# Serial_I2C_Bridge_Prop.net
KiCad netlist of a schematic drawn in EAGLE
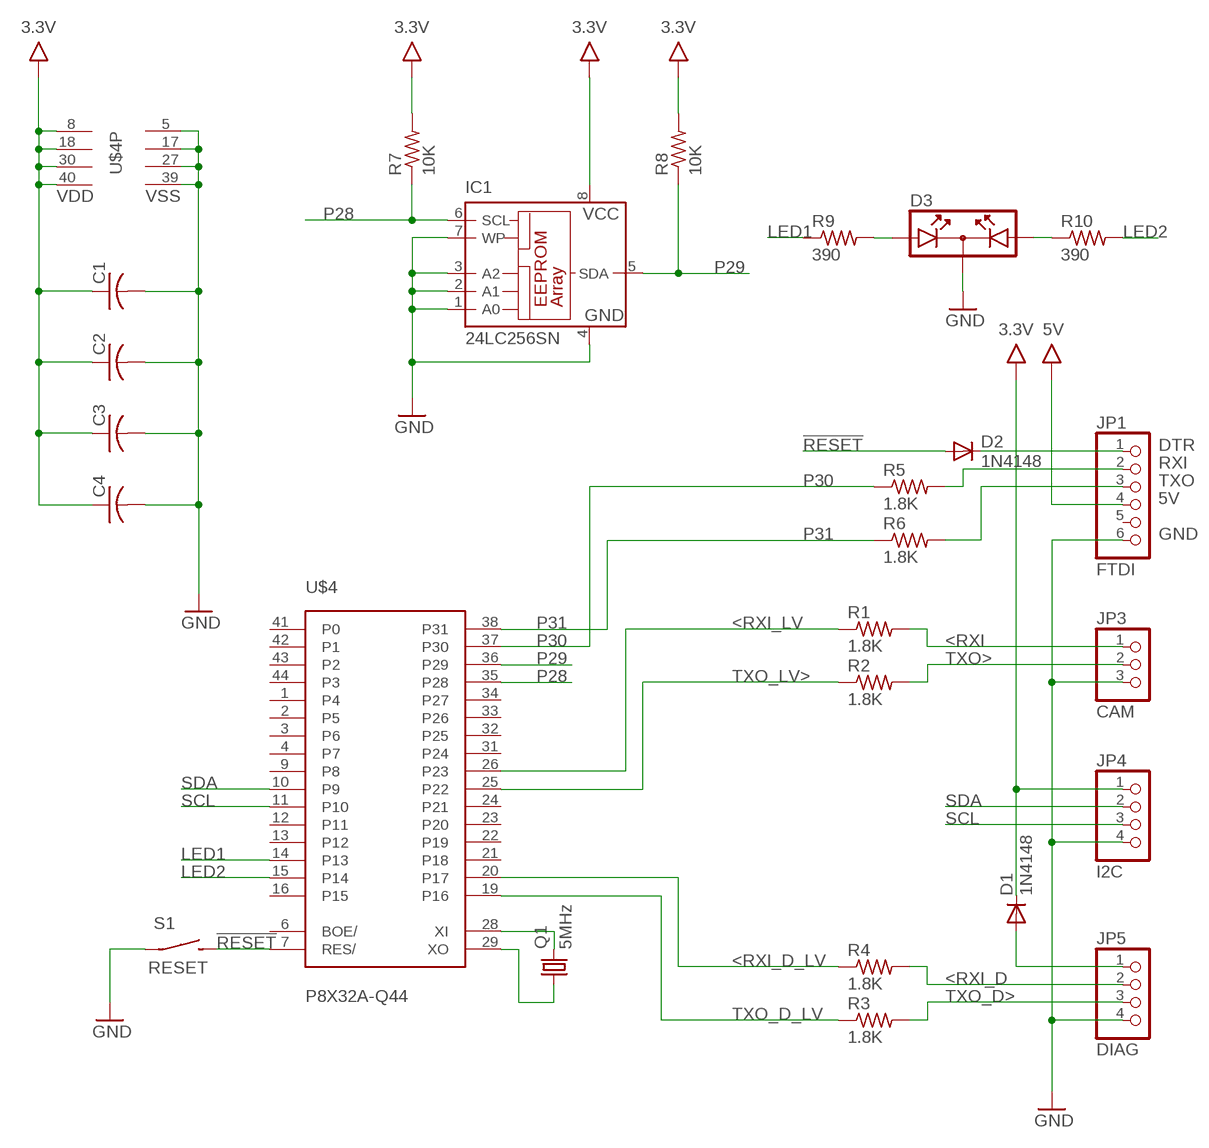
[diagram p0: schematic, sheet 1]

(export (version "E")
  (design (tool "Eeschema 10.0.6"))
  (components
    (comp (ref "C1")
      (value "C-USC0603")
      (footprint "eagle-import:C0603")
      (libsource (lib "eagle-import") (part "C-USC0603"))
    )
    (comp (ref "C2")
      (value "C-USC0603")
      (footprint "eagle-import:C0603")
      (libsource (lib "eagle-import") (part "C-USC0603"))
    )
    (comp (ref "C3")
      (value "C-USC0603")
      (footprint "eagle-import:C0603")
      (libsource (lib "eagle-import") (part "C-USC0603"))
    )
    (comp (ref "C4")
      (value "C-USC0603")
      (footprint "eagle-import:C0603")
      (libsource (lib "eagle-import") (part "C-USC0603"))
    )
    (comp (ref "D1")
      (value "1N4148")
      (footprint "eagle-import:DO35-7")
      (libsource (lib "eagle-import") (part "1N4148DO35-7"))
    )
    (comp (ref "D2")
      (value "1N4148")
      (footprint "eagle-import:DO35-7")
      (libsource (lib "eagle-import") (part "1N4148DO35-7"))
    )
    (comp (ref "D3")
      (value "DUOLED")
      (footprint "eagle-import:DUOLED")
      (libsource (lib "eagle-import") (part "DUOLED"))
    )
    (comp (ref "IC1")
      (value "24LC256SN")
      (footprint "eagle-import:SO-08")
      (fields (field (name "MF") "MICROCHIP") (field (name "MPN") "24LC256-I/SN"))
      (libsource (lib "eagle-import") (part "24SNLC256"))
    )
    (comp (ref "JP1")
      (value "FTDI")
      (footprint "eagle-import:1X06")
      (libsource (lib "eagle-import") (part "PINHD-1X06_2.54"))
    )
    (comp (ref "JP3")
      (value "CAM")
      (footprint "eagle-import:1X03")
      (libsource (lib "eagle-import") (part "PINHD-1X03_2.54"))
    )
    (comp (ref "JP4")
      (value "I2C")
      (footprint "eagle-import:1X04")
      (libsource (lib "eagle-import") (part "PINHD-1X04_2.54"))
    )
    (comp (ref "JP5")
      (value "DIAG")
      (footprint "eagle-import:1X04")
      (libsource (lib "eagle-import") (part "PINHD-1X04_2.54"))
    )
    (comp (ref "Q1")
      (value "5MHz")
      (footprint "eagle-import:HC49_S")
      (libsource (lib "eagle-import") (part "CRYSTALHC49S"))
    )
    (comp (ref "R1")
      (value "1.8K")
      (footprint "eagle-import:0204_5")
      (libsource (lib "eagle-import") (part "R-US_0204/5"))
    )
    (comp (ref "R2")
      (value "1.8K")
      (footprint "eagle-import:0204_5")
      (libsource (lib "eagle-import") (part "R-US_0204/5"))
    )
    (comp (ref "R3")
      (value "1.8K")
      (footprint "eagle-import:0204_5")
      (libsource (lib "eagle-import") (part "R-US_0204/5"))
    )
    (comp (ref "R4")
      (value "1.8K")
      (footprint "eagle-import:0204_5")
      (libsource (lib "eagle-import") (part "R-US_0204/5"))
    )
    (comp (ref "R5")
      (value "1.8K")
      (footprint "eagle-import:0204_5")
      (libsource (lib "eagle-import") (part "R-US_0204/5"))
    )
    (comp (ref "R6")
      (value "1.8K")
      (footprint "eagle-import:0204_5")
      (libsource (lib "eagle-import") (part "R-US_0204/5"))
    )
    (comp (ref "R7")
      (value "10K")
      (footprint "eagle-import:0204_5")
      (libsource (lib "eagle-import") (part "R-US_0204/5"))
    )
    (comp (ref "R8")
      (value "10K")
      (footprint "eagle-import:0204_5")
      (libsource (lib "eagle-import") (part "R-US_0204/5"))
    )
    (comp (ref "R9")
      (value "390")
      (footprint "eagle-import:0204_5")
      (libsource (lib "eagle-import") (part "R-US_0204/5"))
    )
    (comp (ref "R10")
      (value "390")
      (footprint "eagle-import:0204_5")
      (libsource (lib "eagle-import") (part "R-US_0204/5"))
    )
    (comp (ref "S1")
      (value "RESET")
      (footprint "eagle-import:6MMTACTILE")
      (libsource (lib "eagle-import") (part "SPSTTACTILE2"))
    )
    (comp (ref "U$4")
      (value "P8X32A-Q44")
      (footprint "eagle-import:P8X32A-Q44")
      (libsource (lib "eagle-import") (part "P8X32A-Q44"))
    )
  )
  (nets
    (net (code "1") (name "/<RXI") (class "Default")
      (node (ref "JP3") (pin "1") (pinfunction "1_1") (pintype "passive"))
      (node (ref "R1") (pin "2") (pinfunction "2_2") (pintype "passive"))
    )
    (net (code "2") (name "/<RXI_D") (class "Default")
      (node (ref "JP5") (pin "2") (pinfunction "2_2") (pintype "passive"))
      (node (ref "R4") (pin "2") (pinfunction "2_2") (pintype "passive"))
    )
    (net (code "3") (name "/<RXI_D_LV") (class "Default")
      (node (ref "R4") (pin "1") (pinfunction "1_1") (pintype "passive"))
      (node (ref "U$4") (pin "20") (pinfunction "P17_20") (pintype "bidirectional"))
    )
    (net (code "4") (name "/<RXI_LV") (class "Default")
      (node (ref "R1") (pin "1") (pinfunction "1_1") (pintype "passive"))
      (node (ref "U$4") (pin "26") (pinfunction "P23_26") (pintype "bidirectional"))
    )
    (net (code "5") (name "/LED1") (class "Default")
      (node (ref "R9") (pin "1") (pinfunction "1_1") (pintype "passive"))
      (node (ref "U$4") (pin "14") (pinfunction "P13_14") (pintype "bidirectional"))
    )
    (net (code "6") (name "/LED2") (class "Default")
      (node (ref "R10") (pin "2") (pinfunction "2_2") (pintype "passive"))
      (node (ref "U$4") (pin "15") (pinfunction "P14_15") (pintype "bidirectional"))
    )
    (net (code "7") (name "/P28") (class "Default")
      (node (ref "IC1") (pin "6") (pinfunction "SCL_6") (pintype "input"))
      (node (ref "R7") (pin "1") (pinfunction "1_1") (pintype "passive"))
      (node (ref "U$4") (pin "35") (pinfunction "P28_35") (pintype "bidirectional"))
    )
    (net (code "8") (name "/P29") (class "Default")
      (node (ref "IC1") (pin "5") (pinfunction "SDA_5") (pintype "bidirectional"))
      (node (ref "R8") (pin "1") (pinfunction "1_1") (pintype "passive"))
      (node (ref "U$4") (pin "36") (pinfunction "P29_36") (pintype "bidirectional"))
    )
    (net (code "9") (name "/P30") (class "Default")
      (node (ref "R5") (pin "1") (pinfunction "1_1") (pintype "passive"))
      (node (ref "U$4") (pin "37") (pinfunction "P30_37") (pintype "bidirectional"))
    )
    (net (code "10") (name "/P31") (class "Default")
      (node (ref "R6") (pin "1") (pinfunction "1_1") (pintype "passive"))
      (node (ref "U$4") (pin "38") (pinfunction "P31_38") (pintype "bidirectional"))
    )
    (net (code "11") (name "/SCL") (class "Default")
      (node (ref "JP4") (pin "3") (pinfunction "3_3") (pintype "passive"))
      (node (ref "U$4") (pin "11") (pinfunction "P10_11") (pintype "bidirectional"))
    )
    (net (code "12") (name "/SDA") (class "Default")
      (node (ref "JP4") (pin "2") (pinfunction "2_2") (pintype "passive"))
      (node (ref "U$4") (pin "10") (pinfunction "P9_10") (pintype "bidirectional"))
    )
    (net (code "13") (name "/TXO>") (class "Default")
      (node (ref "JP3") (pin "2") (pinfunction "2_2") (pintype "passive"))
      (node (ref "R2") (pin "2") (pinfunction "2_2") (pintype "passive"))
    )
    (net (code "14") (name "/TXO_D>") (class "Default")
      (node (ref "JP5") (pin "3") (pinfunction "3_3") (pintype "passive"))
      (node (ref "R3") (pin "2") (pinfunction "2_2") (pintype "passive"))
    )
    (net (code "15") (name "/TXO_D_LV") (class "Default")
      (node (ref "R3") (pin "1") (pinfunction "1_1") (pintype "passive"))
      (node (ref "U$4") (pin "19") (pinfunction "P16_19") (pintype "bidirectional"))
    )
    (net (code "16") (name "/TXO_LV>") (class "Default")
      (node (ref "R2") (pin "1") (pinfunction "1_1") (pintype "passive"))
      (node (ref "U$4") (pin "25") (pinfunction "P22_25") (pintype "bidirectional"))
    )
    (net (code "17") (name "/~{RESET}") (class "Default")
      (node (ref "D2") (pin "A") (pinfunction "A_A") (pintype "passive"))
      (node (ref "S1") (pin "P$2") (pinfunction "S_P$2") (pintype "passive"))
      (node (ref "U$4") (pin "7") (pinfunction "RES/_7") (pintype "bidirectional"))
    )
    (net (code "18") (name "3.3V") (class "Default")
      (node (ref "C1") (pin "1") (pinfunction "1_1") (pintype "passive"))
      (node (ref "C2") (pin "1") (pinfunction "1_1") (pintype "passive"))
      (node (ref "C3") (pin "1") (pinfunction "1_1") (pintype "passive"))
      (node (ref "C4") (pin "1") (pinfunction "1_1") (pintype "passive"))
      (node (ref "D1") (pin "C") (pinfunction "C_C") (pintype "passive"))
      (node (ref "IC1") (pin "8") (pinfunction "VCC_8") (pintype "power_in"))
      (node (ref "JP4") (pin "1") (pinfunction "1_1") (pintype "passive"))
      (node (ref "R7") (pin "2") (pinfunction "2_2") (pintype "passive"))
      (node (ref "R8") (pin "2") (pinfunction "2_2") (pintype "passive"))
      (node (ref "U$4") (pin "18") (pinfunction "VDD_18") (pintype "power_in"))
      (node (ref "U$4") (pin "30") (pinfunction "VDD_30") (pintype "power_in"))
      (node (ref "U$4") (pin "40") (pinfunction "VDD_40") (pintype "power_in"))
      (node (ref "U$4") (pin "8") (pinfunction "VDD_8") (pintype "power_in"))
    )
    (net (code "19") (name "5V") (class "Default")
      (node (ref "JP1") (pin "4") (pinfunction "4_4") (pintype "passive"))
    )
    (net (code "20") (name "GND") (class "Default")
      (node (ref "C1") (pin "2") (pinfunction "2_2") (pintype "passive"))
      (node (ref "C2") (pin "2") (pinfunction "2_2") (pintype "passive"))
      (node (ref "C3") (pin "2") (pinfunction "2_2") (pintype "passive"))
      (node (ref "C4") (pin "2") (pinfunction "2_2") (pintype "passive"))
      (node (ref "D3") (pin "K") (pinfunction "K_K") (pintype "passive"))
      (node (ref "IC1") (pin "1") (pinfunction "A0_1") (pintype "input"))
      (node (ref "IC1") (pin "2") (pinfunction "A1_2") (pintype "input"))
      (node (ref "IC1") (pin "3") (pinfunction "A2_3") (pintype "input"))
      (node (ref "IC1") (pin "4") (pinfunction "GND_4") (pintype "power_in"))
      (node (ref "IC1") (pin "7") (pinfunction "WP_7") (pintype "input"))
      (node (ref "JP1") (pin "6") (pinfunction "6_6") (pintype "passive"))
      (node (ref "JP3") (pin "3") (pinfunction "3_3") (pintype "passive"))
      (node (ref "JP4") (pin "4") (pinfunction "4_4") (pintype "passive"))
      (node (ref "JP5") (pin "4") (pinfunction "4_4") (pintype "passive"))
      (node (ref "S1") (pin "P$1") (pinfunction "P_P$1") (pintype "passive"))
      (node (ref "U$4") (pin "17") (pinfunction "VSS_17") (pintype "power_in"))
      (node (ref "U$4") (pin "27") (pinfunction "VSS_27") (pintype "power_in"))
      (node (ref "U$4") (pin "39") (pinfunction "VSS_39") (pintype "power_in"))
      (node (ref "U$4") (pin "5") (pinfunction "VSS_5") (pintype "power_in"))
    )
    (net (code "21") (name "Net-(D1-PadA)") (class "Default")
      (node (ref "D1") (pin "A") (pinfunction "A_A") (pintype "passive"))
      (node (ref "JP5") (pin "1") (pinfunction "1_1") (pintype "passive"))
    )
    (net (code "22") (name "Net-(D2-PadC)") (class "Default")
      (node (ref "D2") (pin "C") (pinfunction "C_C") (pintype "passive"))
      (node (ref "JP1") (pin "1") (pinfunction "1_1") (pintype "passive"))
    )
    (net (code "23") (name "Net-(D3-PadA1)") (class "Default")
      (node (ref "D3") (pin "A1") (pinfunction "A1_A1") (pintype "passive"))
      (node (ref "R9") (pin "2") (pinfunction "2_2") (pintype "passive"))
    )
    (net (code "24") (name "Net-(D3-PadA2)") (class "Default")
      (node (ref "D3") (pin "A2") (pinfunction "A2_A2") (pintype "passive"))
      (node (ref "R10") (pin "1") (pinfunction "1_1") (pintype "passive"))
    )
    (net (code "25") (name "Net-(JP1-Pad2)") (class "Default")
      (node (ref "JP1") (pin "2") (pinfunction "2_2") (pintype "passive"))
      (node (ref "R5") (pin "2") (pinfunction "2_2") (pintype "passive"))
    )
    (net (code "26") (name "Net-(JP1-Pad3)") (class "Default")
      (node (ref "JP1") (pin "3") (pinfunction "3_3") (pintype "passive"))
      (node (ref "R6") (pin "2") (pinfunction "2_2") (pintype "passive"))
    )
    (net (code "27") (name "Net-(U$4B-XI)") (class "Default")
      (node (ref "Q1") (pin "2") (pinfunction "2_2") (pintype "passive"))
      (node (ref "U$4") (pin "28") (pinfunction "XI_28") (pintype "input"))
    )
    (net (code "28") (name "Net-(U$4B-XO)") (class "Default")
      (node (ref "Q1") (pin "1") (pinfunction "1_1") (pintype "passive"))
      (node (ref "U$4") (pin "29") (pinfunction "XO_29") (pintype "output"))
    )
    (net (code "29") (name "unconnected-(JP1-Pad5)") (class "Default")
      (node (ref "JP1") (pin "5") (pinfunction "5_5") (pintype "passive"))
    )
    (net (code "30") (name "unconnected-(U$4B-BOE{slash}-Pad6)") (class "Default")
      (node (ref "U$4") (pin "6") (pinfunction "BOE/_6") (pintype "input"))
    )
    (net (code "31") (name "unconnected-(U$4B-P0-Pad41)") (class "Default")
      (node (ref "U$4") (pin "41") (pinfunction "P0_41") (pintype "bidirectional"))
    )
    (net (code "32") (name "unconnected-(U$4B-P1-Pad42)") (class "Default")
      (node (ref "U$4") (pin "42") (pinfunction "P1_42") (pintype "bidirectional"))
    )
    (net (code "33") (name "unconnected-(U$4B-P2-Pad43)") (class "Default")
      (node (ref "U$4") (pin "43") (pinfunction "P2_43") (pintype "bidirectional"))
    )
    (net (code "34") (name "unconnected-(U$4B-P3-Pad44)") (class "Default")
      (node (ref "U$4") (pin "44") (pinfunction "P3_44") (pintype "bidirectional"))
    )
    (net (code "35") (name "unconnected-(U$4B-P4-Pad1)") (class "Default")
      (node (ref "U$4") (pin "1") (pinfunction "P4_1") (pintype "bidirectional"))
    )
    (net (code "36") (name "unconnected-(U$4B-P5-Pad2)") (class "Default")
      (node (ref "U$4") (pin "2") (pinfunction "P5_2") (pintype "bidirectional"))
    )
    (net (code "37") (name "unconnected-(U$4B-P6-Pad3)") (class "Default")
      (node (ref "U$4") (pin "3") (pinfunction "P6_3") (pintype "bidirectional"))
    )
    (net (code "38") (name "unconnected-(U$4B-P7-Pad4)") (class "Default")
      (node (ref "U$4") (pin "4") (pinfunction "P7_4") (pintype "bidirectional"))
    )
    (net (code "39") (name "unconnected-(U$4B-P8-Pad9)") (class "Default")
      (node (ref "U$4") (pin "9") (pinfunction "P8_9") (pintype "bidirectional"))
    )
    (net (code "40") (name "unconnected-(U$4B-P11-Pad12)") (class "Default")
      (node (ref "U$4") (pin "12") (pinfunction "P11_12") (pintype "bidirectional"))
    )
    (net (code "41") (name "unconnected-(U$4B-P12-Pad13)") (class "Default")
      (node (ref "U$4") (pin "13") (pinfunction "P12_13") (pintype "bidirectional"))
    )
    (net (code "42") (name "unconnected-(U$4B-P15-Pad16)") (class "Default")
      (node (ref "U$4") (pin "16") (pinfunction "P15_16") (pintype "bidirectional"))
    )
    (net (code "43") (name "unconnected-(U$4B-P18-Pad21)") (class "Default")
      (node (ref "U$4") (pin "21") (pinfunction "P18_21") (pintype "bidirectional"))
    )
    (net (code "44") (name "unconnected-(U$4B-P19-Pad22)") (class "Default")
      (node (ref "U$4") (pin "22") (pinfunction "P19_22") (pintype "bidirectional"))
    )
    (net (code "45") (name "unconnected-(U$4B-P20-Pad23)") (class "Default")
      (node (ref "U$4") (pin "23") (pinfunction "P20_23") (pintype "bidirectional"))
    )
    (net (code "46") (name "unconnected-(U$4B-P21-Pad24)") (class "Default")
      (node (ref "U$4") (pin "24") (pinfunction "P21_24") (pintype "bidirectional"))
    )
    (net (code "47") (name "unconnected-(U$4B-P24-Pad31)") (class "Default")
      (node (ref "U$4") (pin "31") (pinfunction "P24_31") (pintype "bidirectional"))
    )
    (net (code "48") (name "unconnected-(U$4B-P25-Pad32)") (class "Default")
      (node (ref "U$4") (pin "32") (pinfunction "P25_32") (pintype "bidirectional"))
    )
    (net (code "49") (name "unconnected-(U$4B-P26-Pad33)") (class "Default")
      (node (ref "U$4") (pin "33") (pinfunction "P26_33") (pintype "bidirectional"))
    )
    (net (code "50") (name "unconnected-(U$4B-P27-Pad34)") (class "Default")
      (node (ref "U$4") (pin "34") (pinfunction "P27_34") (pintype "bidirectional"))
    )
  )
)
